# working.net
KiCad netlist of a schematic drawn in EAGLE
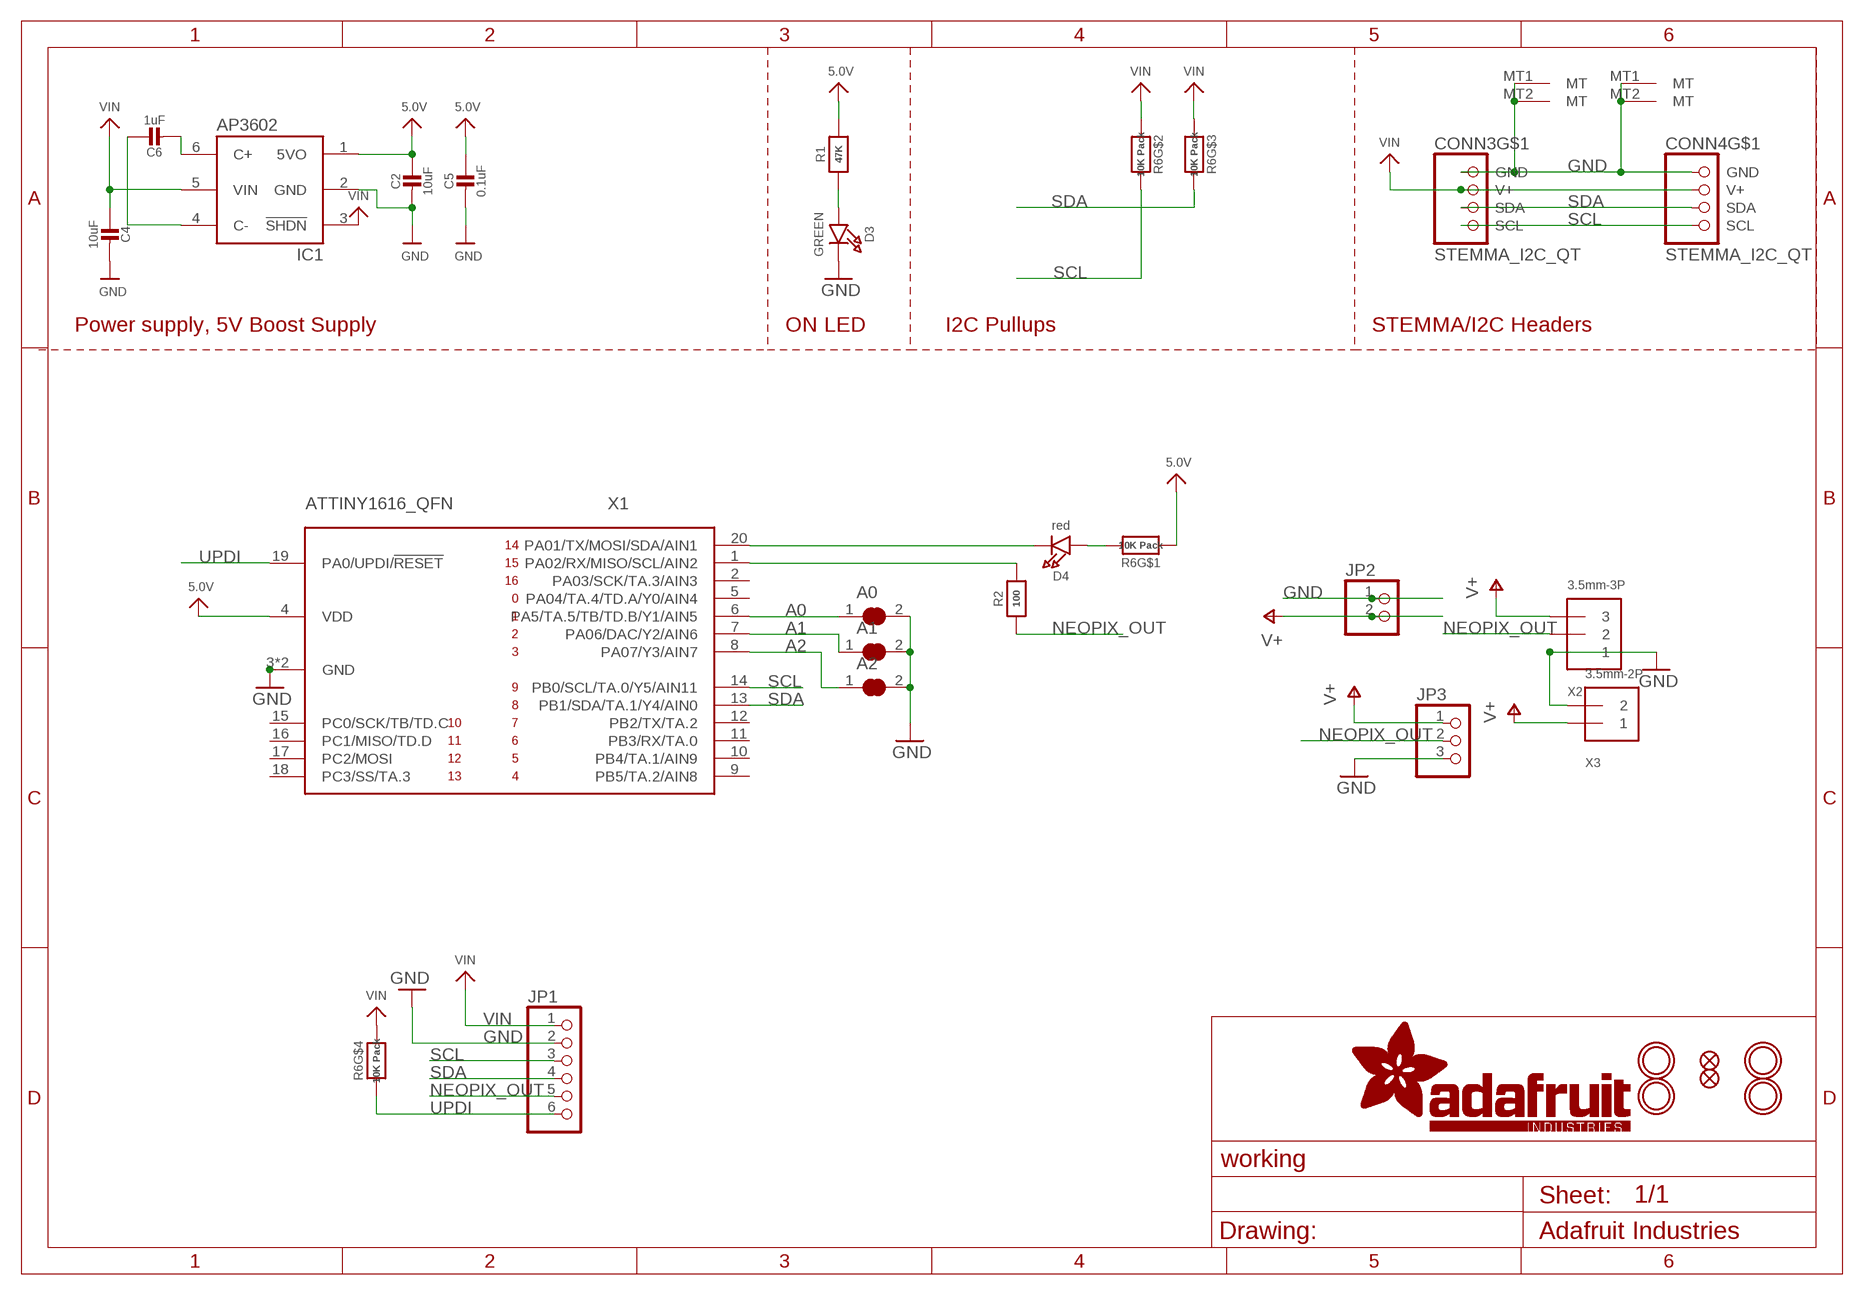
[diagram p0: schematic, sheet 1]

(export (version "E")
  (design (tool "Eeschema 10.0.6"))
  (components
    (comp (ref "A0")
      (value "SOLDERJUMPER_CLOSED")
      (footprint "eagle-import:SOLDERJUMPER_CLOSEDWIRE")
      (libsource (lib "eagle-import") (part "SOLDERJUMPER_CLOSED"))
    )
    (comp (ref "A1")
      (value "SOLDERJUMPER_CLOSED")
      (footprint "eagle-import:SOLDERJUMPER_CLOSEDWIRE")
      (libsource (lib "eagle-import") (part "SOLDERJUMPER_CLOSED"))
    )
    (comp (ref "A2")
      (value "SOLDERJUMPER_CLOSED")
      (footprint "eagle-import:SOLDERJUMPER_CLOSEDWIRE")
      (libsource (lib "eagle-import") (part "SOLDERJUMPER_CLOSED"))
    )
    (comp (ref "C2")
      (value "10uF")
      (footprint "eagle-import:0805-NO")
      (libsource (lib "eagle-import") (part "CAP_CERAMIC0805-NOOUTLINE"))
    )
    (comp (ref "C4")
      (value "10uF")
      (footprint "eagle-import:0805-NO")
      (libsource (lib "eagle-import") (part "CAP_CERAMIC0805-NOOUTLINE"))
    )
    (comp (ref "C5")
      (value "0.1uF")
      (footprint "eagle-import:0603-NO")
      (libsource (lib "eagle-import") (part "CAP_CERAMIC0603_NO"))
    )
    (comp (ref "C6")
      (value "1uF")
      (footprint "eagle-import:0603-NO")
      (libsource (lib "eagle-import") (part "CAP_CERAMIC0603_NO"))
    )
    (comp (ref "CONN3")
      (value "STEMMA_I2C_QT")
      (footprint "eagle-import:JST_SH4")
      (libsource (lib "eagle-import") (part "STEMMA_I2C_QT"))
    )
    (comp (ref "CONN4")
      (value "STEMMA_I2C_QT")
      (footprint "eagle-import:JST_SH4")
      (libsource (lib "eagle-import") (part "STEMMA_I2C_QT"))
    )
    (comp (ref "D3")
      (value "GREEN")
      (footprint "eagle-import:CHIPLED_0603_NOOUTLINE")
      (libsource (lib "eagle-import") (part "LED0603_NOOUTLINE"))
    )
    (comp (ref "D4")
      (value "red")
      (footprint "eagle-import:CHIPLED_0603_NOOUTLINE")
      (libsource (lib "eagle-import") (part "LED0603_NOOUTLINE"))
    )
    (comp (ref "FID1")
      (value "FIDUCIAL_1MM")
      (footprint "eagle-import:FIDUCIAL_1MM")
      (libsource (lib "eagle-import") (part "FIDUCIAL_1MM"))
    )
    (comp (ref "FID2")
      (value "FIDUCIAL_1MM")
      (footprint "eagle-import:FIDUCIAL_1MM")
      (libsource (lib "eagle-import") (part "FIDUCIAL_1MM"))
    )
    (comp (ref "IC1")
      (value "AP3602")
      (footprint "eagle-import:SOT23-6")
      (libsource (lib "eagle-import") (part "AP3602"))
    )
    (comp (ref "JP1")
      (value "HEADER-1X670MIL")
      (footprint "eagle-import:1X06_ROUND_70")
      (libsource (lib "eagle-import") (part "HEADER-1X670MIL"))
    )
    (comp (ref "JP2")
      (value "HEADER-1X2ROUND")
      (footprint "eagle-import:1X02_ROUND")
      (libsource (lib "eagle-import") (part "HEADER-1X2ROUND"))
    )
    (comp (ref "JP3")
      (value "HEADER-1X3ROUND")
      (footprint "eagle-import:1X03_ROUND")
      (libsource (lib "eagle-import") (part "HEADER-1X3ROUND"))
    )
    (comp (ref "R1")
      (value "47K")
      (footprint "eagle-import:0603-NO")
      (libsource (lib "eagle-import") (part "RESISTOR_0603_NOOUT"))
    )
    (comp (ref "R2")
      (value "100")
      (footprint "eagle-import:0603-NO")
      (libsource (lib "eagle-import") (part "RESISTOR_0603_NOOUT"))
    )
    (comp (ref "R6")
      (value "10K Pack")
      (footprint "eagle-import:RESPACK_4X0603")
      (libsource (lib "eagle-import") (part "RESISTOR_4PACK"))
    )
    (comp (ref "U$1")
      (value "MOUNTINGHOLE2.5")
      (footprint "eagle-import:MOUNTINGHOLE_2.5_PLATED")
      (libsource (lib "eagle-import") (part "MOUNTINGHOLE2.5"))
    )
    (comp (ref "U$6")
      (value "MOUNTINGHOLE2.5")
      (footprint "eagle-import:MOUNTINGHOLE_2.5_PLATED")
      (libsource (lib "eagle-import") (part "MOUNTINGHOLE2.5"))
    )
    (comp (ref "U$9")
      (value "MOUNTINGHOLE2.5")
      (footprint "eagle-import:MOUNTINGHOLE_2.5_PLATED")
      (libsource (lib "eagle-import") (part "MOUNTINGHOLE2.5"))
    )
    (comp (ref "U$18")
      (value "MOUNTINGHOLE2.5")
      (footprint "eagle-import:MOUNTINGHOLE_2.5_PLATED")
      (libsource (lib "eagle-import") (part "MOUNTINGHOLE2.5"))
    )
    (comp (ref "X1")
      (value "ATTINY1616_QFN")
      (footprint "eagle-import:QFN20_3MM")
      (libsource (lib "eagle-import") (part "ATTINY8X6_QFN"))
    )
    (comp (ref "X2")
      (value "3.5mm-3P")
      (footprint "eagle-import:TERMBLOCK_1X3-3.5MM")
      (libsource (lib "eagle-import") (part "TERMBLOCK_1X3"))
    )
    (comp (ref "X3")
      (value "3.5mm-2P")
      (footprint "eagle-import:TERMBLOCK_1X2-3.5MM")
      (libsource (lib "eagle-import") (part "TERMBLOCK_1X2_3.5MM"))
    )
  )
  (nets
    (net (code "1") (name "/A0") (class "Default")
      (node (ref "A0") (pin "1") (pinfunction "1_1") (pintype "passive"))
      (node (ref "X1") (pin "6") (pinfunction "PA5/TA.5/TB/TD.B/Y1/AIN5_6") (pintype "bidirectional"))
    )
    (net (code "2") (name "/A1") (class "Default")
      (node (ref "A1") (pin "1") (pinfunction "1_1") (pintype "passive"))
      (node (ref "X1") (pin "7") (pinfunction "PA06/DAC/Y2/AIN6_7") (pintype "bidirectional"))
    )
    (net (code "3") (name "/A2") (class "Default")
      (node (ref "A2") (pin "1") (pinfunction "1_1") (pintype "passive"))
      (node (ref "X1") (pin "8") (pinfunction "PA07/Y3/AIN7_8") (pintype "bidirectional"))
    )
    (net (code "4") (name "/NEOPIX_OUT") (class "Default")
      (node (ref "JP1") (pin "5") (pinfunction "5_5") (pintype "passive"))
      (node (ref "JP3") (pin "2") (pinfunction "2_2") (pintype "passive"))
      (node (ref "R2") (pin "1") (pinfunction "1_1") (pintype "passive"))
      (node (ref "X2") (pin "2") (pinfunction "2_2") (pintype "passive"))
    )
    (net (code "5") (name "/SCL") (class "Default")
      (node (ref "CONN3") (pin "4") (pinfunction "SCL_4") (pintype "passive"))
      (node (ref "CONN4") (pin "4") (pinfunction "SCL_4") (pintype "passive"))
      (node (ref "JP1") (pin "3") (pinfunction "3_3") (pintype "passive"))
      (node (ref "R6") (pin "7") (pinfunction "2_7") (pintype "passive"))
      (node (ref "X1") (pin "14") (pinfunction "PB0/SCL/TA.0/Y5/AIN11_14") (pintype "bidirectional"))
    )
    (net (code "6") (name "/SDA") (class "Default")
      (node (ref "CONN3") (pin "3") (pinfunction "SDA_3") (pintype "passive"))
      (node (ref "CONN4") (pin "3") (pinfunction "SDA_3") (pintype "passive"))
      (node (ref "JP1") (pin "4") (pinfunction "4_4") (pintype "passive"))
      (node (ref "R6") (pin "6") (pinfunction "2_6") (pintype "passive"))
      (node (ref "X1") (pin "13") (pinfunction "PB1/SDA/TA.1/Y4/AIN0_13") (pintype "bidirectional"))
    )
    (net (code "7") (name "/UPDI") (class "Default")
      (node (ref "JP1") (pin "6") (pinfunction "6_6") (pintype "passive"))
      (node (ref "R6") (pin "4") (pinfunction "1_4") (pintype "passive"))
      (node (ref "X1") (pin "19") (pinfunction "PA0/UPDI/~{RESET}_19") (pintype "bidirectional"))
    )
    (net (code "8") (name "5.0V") (class "Default")
      (node (ref "C2") (pin "1") (pinfunction "1_1") (pintype "passive"))
      (node (ref "C5") (pin "1") (pinfunction "1_1") (pintype "passive"))
      (node (ref "IC1") (pin "1") (pinfunction "5VO_1") (pintype "power_in"))
      (node (ref "R1") (pin "2") (pinfunction "2_2") (pintype "passive"))
      (node (ref "R6") (pin "1") (pinfunction "1_1") (pintype "passive"))
      (node (ref "X1") (pin "4") (pinfunction "VDD_4") (pintype "power_in"))
    )
    (net (code "9") (name "GND") (class "Default")
      (node (ref "A0") (pin "2") (pinfunction "2_2") (pintype "passive"))
      (node (ref "A1") (pin "2") (pinfunction "2_2") (pintype "passive"))
      (node (ref "A2") (pin "2") (pinfunction "2_2") (pintype "passive"))
      (node (ref "C2") (pin "2") (pinfunction "2_2") (pintype "passive"))
      (node (ref "C4") (pin "2") (pinfunction "2_2") (pintype "passive"))
      (node (ref "C5") (pin "2") (pinfunction "2_2") (pintype "passive"))
      (node (ref "CONN3") (pin "1") (pinfunction "GND_1") (pintype "passive"))
      (node (ref "CONN3") (pin "MT1") (pinfunction "MT_MT1") (pintype "bidirectional"))
      (node (ref "CONN3") (pin "MT2") (pinfunction "MT_MT2") (pintype "bidirectional"))
      (node (ref "CONN4") (pin "1") (pinfunction "GND_1") (pintype "passive"))
      (node (ref "CONN4") (pin "MT1") (pinfunction "MT_MT1") (pintype "bidirectional"))
      (node (ref "CONN4") (pin "MT2") (pinfunction "MT_MT2") (pintype "bidirectional"))
      (node (ref "D3") (pin "C") (pinfunction "C_C") (pintype "passive"))
      (node (ref "IC1") (pin "2") (pinfunction "GND_2") (pintype "power_in"))
      (node (ref "JP1") (pin "2") (pinfunction "2_2") (pintype "passive"))
      (node (ref "JP2") (pin "1") (pinfunction "1_1") (pintype "passive"))
      (node (ref "JP3") (pin "3") (pinfunction "3_3") (pintype "passive"))
      (node (ref "X1") (pin "3") (pinfunction "GND_3") (pintype "power_in"))
      (node (ref "X1") (pin "PAD") (pinfunction "GND_PAD") (pintype "power_in"))
      (node (ref "X2") (pin "1") (pinfunction "1_1") (pintype "passive"))
      (node (ref "X3") (pin "2") (pinfunction "2_2") (pintype "passive"))
    )
    (net (code "10") (name "Net-(D3-PadA)") (class "Default")
      (node (ref "D3") (pin "A") (pinfunction "A_A") (pintype "passive"))
      (node (ref "R1") (pin "1") (pinfunction "1_1") (pintype "passive"))
    )
    (net (code "11") (name "Net-(IC1-C+)") (class "Default")
      (node (ref "C6") (pin "2") (pinfunction "2_2") (pintype "passive"))
      (node (ref "IC1") (pin "6") (pinfunction "C+_6") (pintype "bidirectional"))
    )
    (net (code "12") (name "Net-(IC1-C-)") (class "Default")
      (node (ref "C6") (pin "1") (pinfunction "1_1") (pintype "passive"))
      (node (ref "IC1") (pin "4") (pinfunction "C-_4") (pintype "bidirectional"))
    )
    (net (code "13") (name "Net-(R6A-2)") (class "Default")
      (node (ref "D4") (pin "A") (pinfunction "A_A") (pintype "passive"))
      (node (ref "R6") (pin "8") (pinfunction "2_8") (pintype "passive"))
    )
    (net (code "14") (name "Net-(X1-PA01{slash}TX{slash}MOSI{slash}SDA{slash}AIN1)") (class "Default")
      (node (ref "D4") (pin "C") (pinfunction "C_C") (pintype "passive"))
      (node (ref "X1") (pin "20") (pinfunction "PA01/TX/MOSI/SDA/AIN1_20") (pintype "bidirectional"))
    )
    (net (code "15") (name "Net-(X1-PA02{slash}RX{slash}MISO{slash}SCL{slash}AIN2)") (class "Default")
      (node (ref "R2") (pin "2") (pinfunction "2_2") (pintype "passive"))
      (node (ref "X1") (pin "1") (pinfunction "PA02/RX/MISO/SCL/AIN2_1") (pintype "bidirectional"))
    )
    (net (code "16") (name "V+") (class "Default")
      (node (ref "JP2") (pin "2") (pinfunction "2_2") (pintype "passive"))
      (node (ref "JP3") (pin "1") (pinfunction "1_1") (pintype "passive"))
      (node (ref "X2") (pin "3") (pinfunction "3_3") (pintype "passive"))
      (node (ref "X3") (pin "1") (pinfunction "1_1") (pintype "passive"))
    )
    (net (code "17") (name "VIN") (class "Default")
      (node (ref "C4") (pin "1") (pinfunction "1_1") (pintype "passive"))
      (node (ref "CONN3") (pin "2") (pinfunction "V+_2") (pintype "passive"))
      (node (ref "CONN4") (pin "2") (pinfunction "V+_2") (pintype "passive"))
      (node (ref "IC1") (pin "3") (pinfunction "~{SHDN}_3") (pintype "input"))
      (node (ref "IC1") (pin "5") (pinfunction "VIN_5") (pintype "power_in"))
      (node (ref "JP1") (pin "1") (pinfunction "1_1") (pintype "passive"))
      (node (ref "R6") (pin "2") (pinfunction "1_2") (pintype "passive"))
      (node (ref "R6") (pin "3") (pinfunction "1_3") (pintype "passive"))
      (node (ref "R6") (pin "5") (pinfunction "2_5") (pintype "passive"))
    )
    (net (code "18") (name "unconnected-(X1-PA03{slash}SCK{slash}TA.3{slash}AIN3-Pad2)") (class "Default")
      (node (ref "X1") (pin "2") (pinfunction "PA03/SCK/TA.3/AIN3_2") (pintype "bidirectional"))
    )
    (net (code "19") (name "unconnected-(X1-PA04{slash}TA.4{slash}TD.A{slash}Y0{slash}AIN4-Pad5)") (class "Default")
      (node (ref "X1") (pin "5") (pinfunction "PA04/TA.4/TD.A/Y0/AIN4_5") (pintype "bidirectional"))
    )
    (net (code "20") (name "unconnected-(X1-PB2{slash}TX{slash}TA.2-Pad12)") (class "Default")
      (node (ref "X1") (pin "12") (pinfunction "PB2/TX/TA.2_12") (pintype "bidirectional"))
    )
    (net (code "21") (name "unconnected-(X1-PB3{slash}RX{slash}TA.0-Pad11)") (class "Default")
      (node (ref "X1") (pin "11") (pinfunction "PB3/RX/TA.0_11") (pintype "bidirectional"))
    )
    (net (code "22") (name "unconnected-(X1-PB4{slash}TA.1{slash}AIN9-Pad10)") (class "Default")
      (node (ref "X1") (pin "10") (pinfunction "PB4/TA.1/AIN9_10") (pintype "bidirectional"))
    )
    (net (code "23") (name "unconnected-(X1-PB5{slash}TA.2{slash}AIN8-Pad9)") (class "Default")
      (node (ref "X1") (pin "9") (pinfunction "PB5/TA.2/AIN8_9") (pintype "bidirectional"))
    )
    (net (code "24") (name "unconnected-(X1-PC0{slash}SCK{slash}TB{slash}TD.C-Pad15)") (class "Default")
      (node (ref "X1") (pin "15") (pinfunction "PC0/SCK/TB/TD.C_15") (pintype "bidirectional"))
    )
    (net (code "25") (name "unconnected-(X1-PC1{slash}MISO{slash}TD.D-Pad16)") (class "Default")
      (node (ref "X1") (pin "16") (pinfunction "PC1/MISO/TD.D_16") (pintype "bidirectional"))
    )
    (net (code "26") (name "unconnected-(X1-PC2{slash}MOSI-Pad17)") (class "Default")
      (node (ref "X1") (pin "17") (pinfunction "PC2/MOSI_17") (pintype "bidirectional"))
    )
    (net (code "27") (name "unconnected-(X1-PC3{slash}SS{slash}TA.3-Pad18)") (class "Default")
      (node (ref "X1") (pin "18") (pinfunction "PC3/SS/TA.3_18") (pintype "bidirectional"))
    )
  )
)
